# sensor.net
KiCad netlist of a schematic drawn in EAGLE
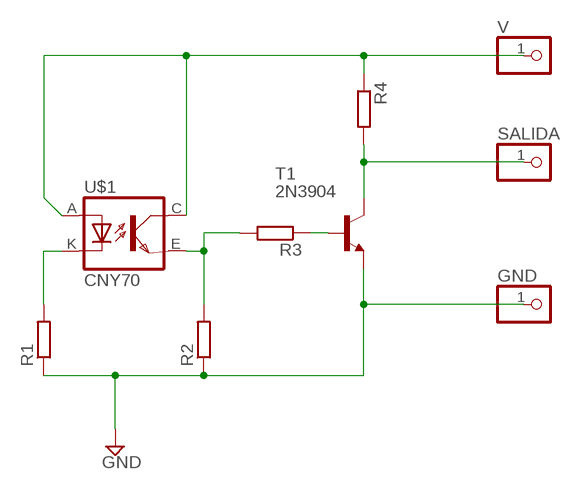
[diagram p0: schematic, sheet 1]

(export (version "E")
  (design (tool "Eeschema 10.0.6"))
  (components
    (comp (ref "GND")
      (value "PINHD-1X1")
      (footprint "eagle-import:1X01")
      (libsource (lib "eagle-import") (part "PINHD-1X1"))
    )
    (comp (ref "R1")
      (value "R-EU_0207/10")
      (footprint "eagle-import:0207_10")
      (libsource (lib "eagle-import") (part "R-EU_0207/10"))
    )
    (comp (ref "R2")
      (value "R-EU_0207/10")
      (footprint "eagle-import:0207_10")
      (libsource (lib "eagle-import") (part "R-EU_0207/10"))
    )
    (comp (ref "R3")
      (value "R-EU_0207/10")
      (footprint "eagle-import:0207_10")
      (libsource (lib "eagle-import") (part "R-EU_0207/10"))
    )
    (comp (ref "R4")
      (value "R-EU_0207/10")
      (footprint "eagle-import:0207_10")
      (libsource (lib "eagle-import") (part "R-EU_0207/10"))
    )
    (comp (ref "SALIDA")
      (value "PINHD-1X1")
      (footprint "eagle-import:1X01")
      (libsource (lib "eagle-import") (part "PINHD-1X1"))
    )
    (comp (ref "T1")
      (value "2N3904")
      (footprint "eagle-import:TO92")
      (libsource (lib "eagle-import") (part "2N3904"))
    )
    (comp (ref "U$1")
      (value "CNY70")
      (footprint "eagle-import:4")
      (libsource (lib "eagle-import") (part "CNY70"))
    )
    (comp (ref "V")
      (value "PINHD-1X1")
      (footprint "eagle-import:1X01")
      (libsource (lib "eagle-import") (part "PINHD-1X1"))
    )
  )
  (nets
    (net (code "1") (name "GND") (class "Default")
      (node (ref "GND") (pin "1") (pinfunction "1_1") (pintype "passive"))
      (node (ref "R1") (pin "1") (pinfunction "1_1") (pintype "passive"))
      (node (ref "R2") (pin "1") (pinfunction "1_1") (pintype "passive"))
      (node (ref "T1") (pin "3") (pinfunction "E_3") (pintype "passive"))
    )
    (net (code "2") (name "Net-(T1-B)") (class "Default")
      (node (ref "R3") (pin "1") (pinfunction "1_1") (pintype "passive"))
      (node (ref "T1") (pin "2") (pinfunction "B_2") (pintype "passive"))
    )
    (net (code "3") (name "Net-(T1-C)") (class "Default")
      (node (ref "R4") (pin "2") (pinfunction "2_2") (pintype "passive"))
      (node (ref "SALIDA") (pin "1") (pinfunction "1_1") (pintype "passive"))
      (node (ref "T1") (pin "1") (pinfunction "C_1") (pintype "passive"))
    )
    (net (code "4") (name "Net-(U$1-C)") (class "Default")
      (node (ref "R1") (pin "2") (pinfunction "2_2") (pintype "passive"))
      (node (ref "U$1") (pin "K") (pinfunction "C_K") (pintype "passive"))
    )
    (net (code "5") (name "Net-(U$1-COL)") (class "Default")
      (node (ref "R4") (pin "1") (pinfunction "1_1") (pintype "passive"))
      (node (ref "U$1") (pin "A") (pinfunction "A_A") (pintype "passive"))
      (node (ref "U$1") (pin "C") (pinfunction "COL_C") (pintype "passive"))
      (node (ref "V") (pin "1") (pinfunction "1_1") (pintype "passive"))
    )
    (net (code "6") (name "Net-(U$1-EMI)") (class "Default")
      (node (ref "R2") (pin "2") (pinfunction "2_2") (pintype "passive"))
      (node (ref "R3") (pin "2") (pinfunction "2_2") (pintype "passive"))
      (node (ref "U$1") (pin "E") (pinfunction "EMI_E") (pintype "passive"))
    )
  )
)
